# pcb.net
KiCad netlist of a schematic drawn in EasyEDA
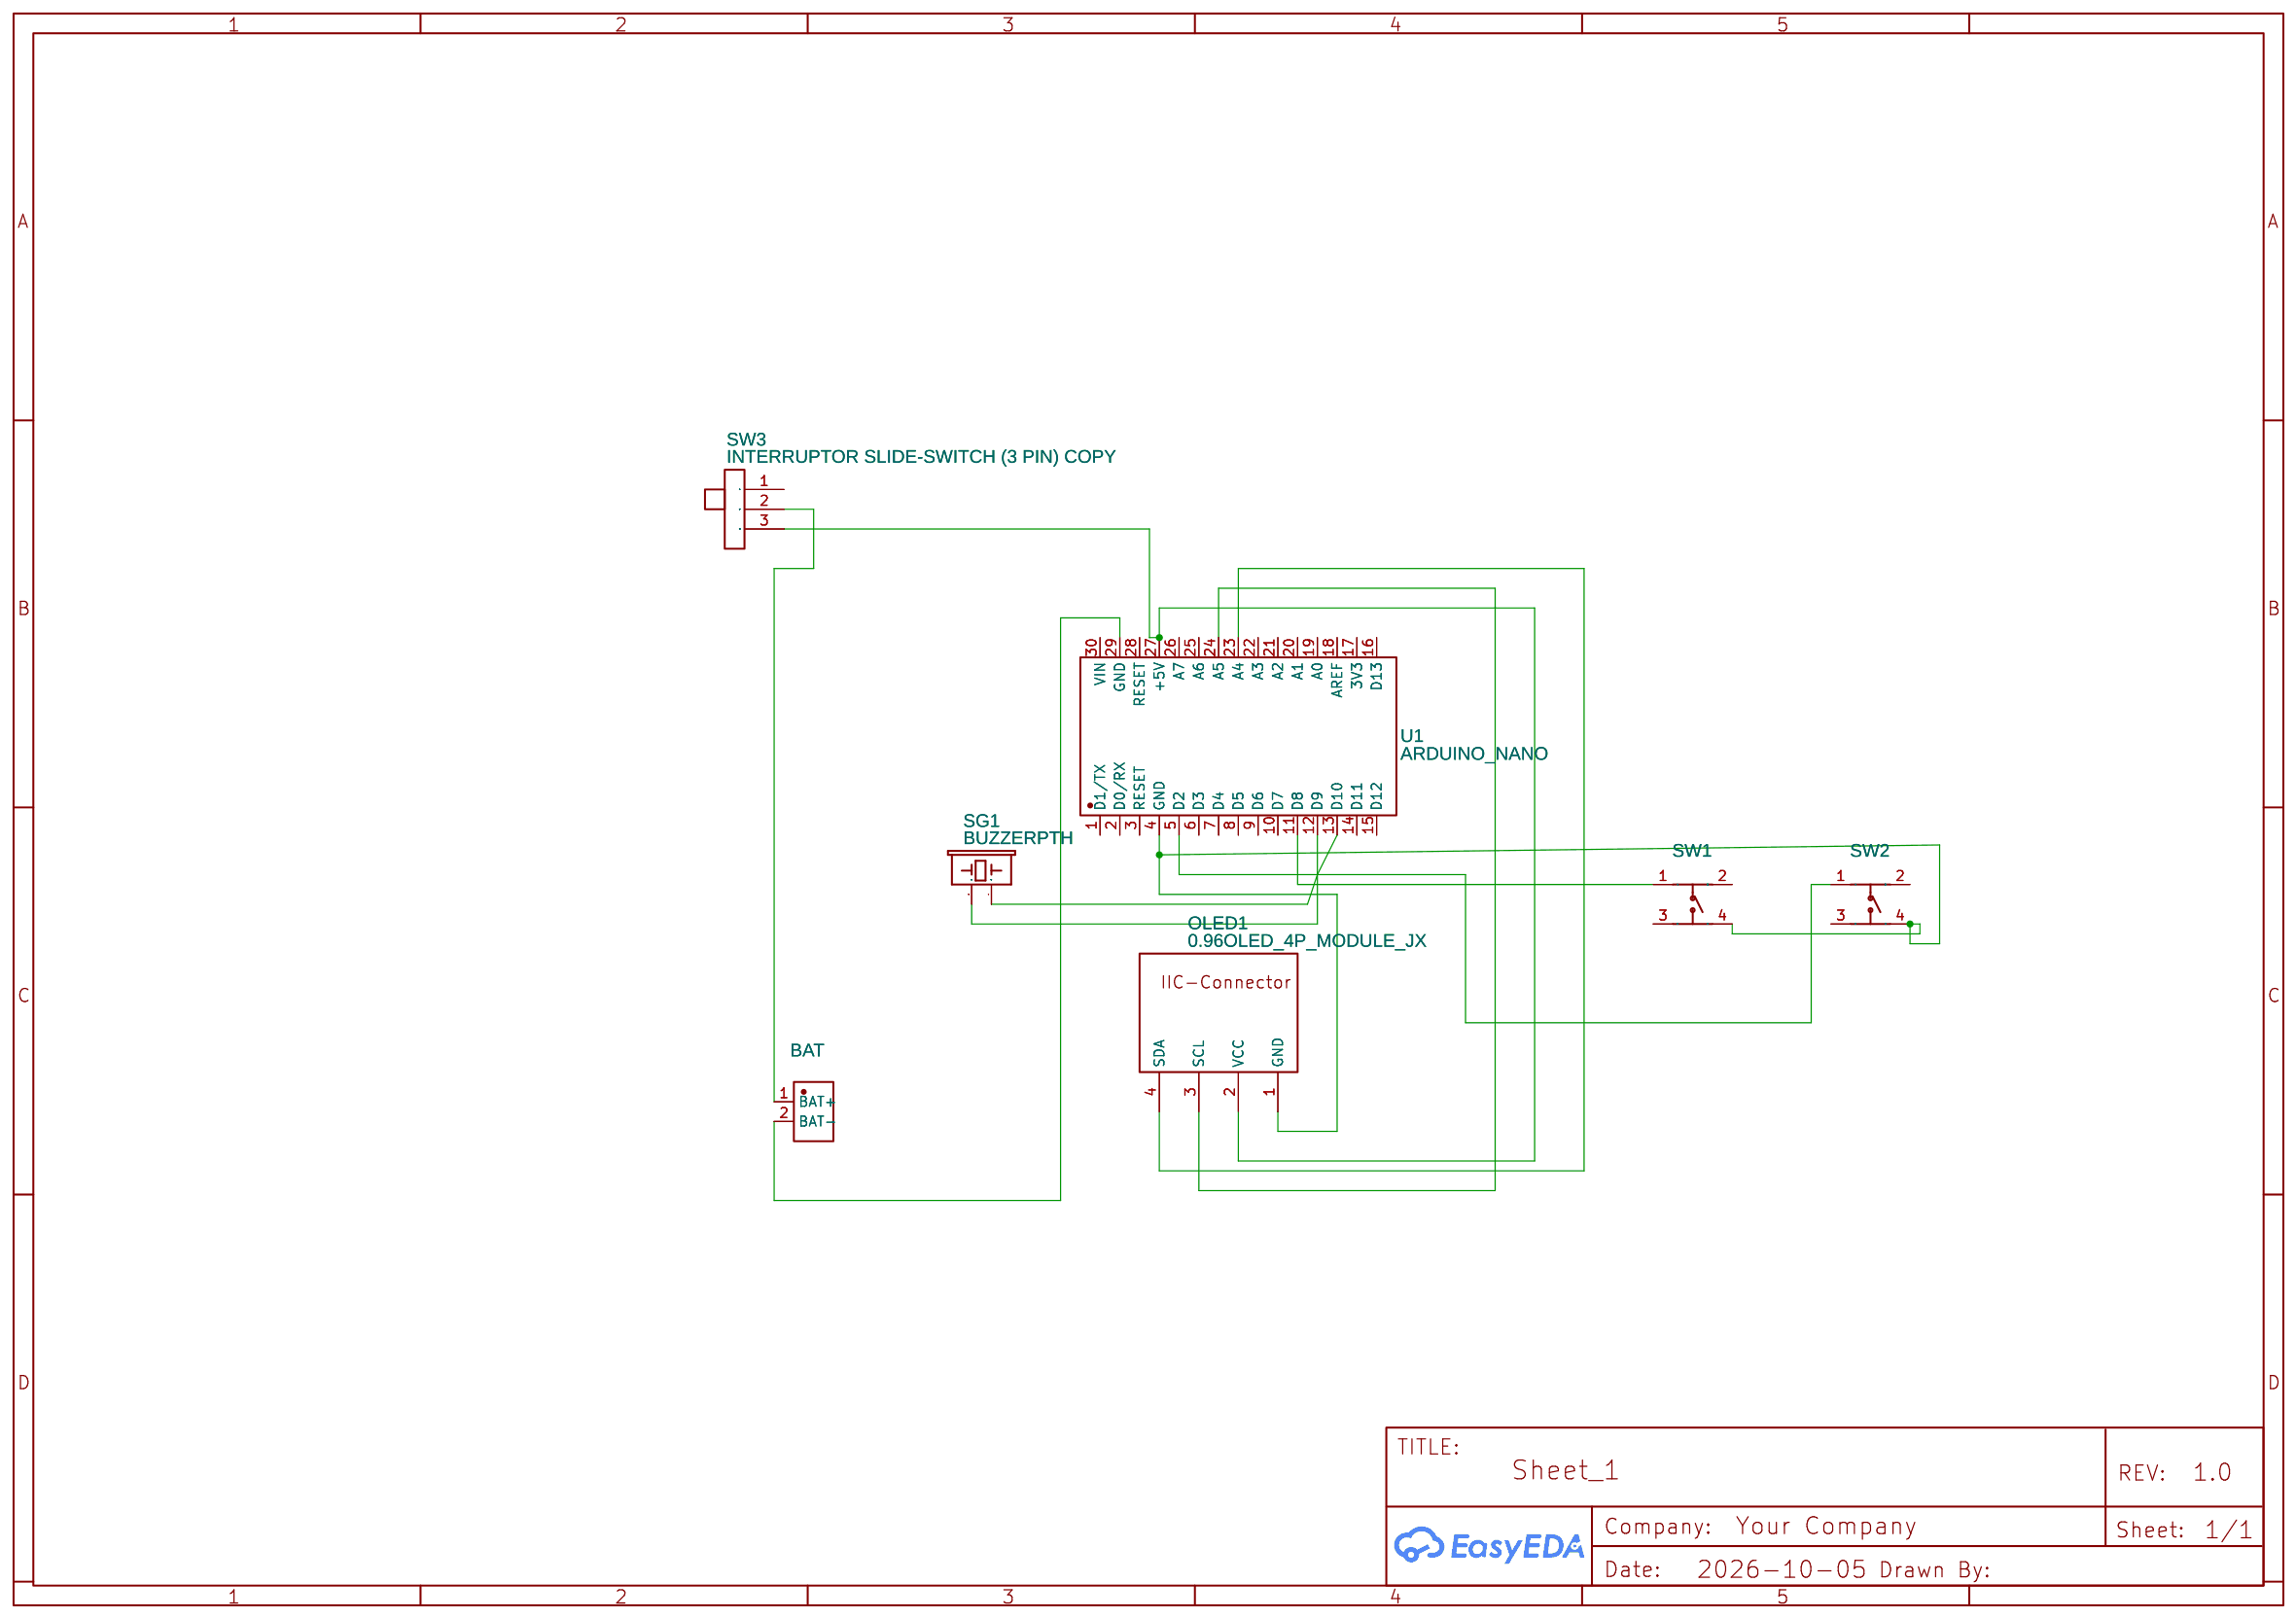
[diagram p0: schematic sheet]

(export (version "E")
  (design (tool "Eeschema 10.0.6"))
  (components
    (comp (ref "BAT")
      (value "880-70-002-10-001101")
      (fields (field (name "Manufacturer") "Preci-Dip"))
      (libsource (lib "") (part "880-70-002-10-001101"))
    )
    (comp (ref "OLED1") (value "0.96OLED_4P_MODULE_JX") (libsource (lib "") (part "0.96OLED_4P_MODULE_JX")))
    (comp (ref "SG1") (value "BUZZERPTH") (libsource (lib "") (part "BUZZERPTH")))
    (comp (ref "SW1")
      (value "SW1")
      (fields (field (name "Manufacturer Part") "Buttontact-6x6mm"))
      (libsource (lib "") (part "BUTTONTACT-6X6MM"))
    )
    (comp (ref "SW2")
      (value "SW2")
      (fields (field (name "Manufacturer Part") "Buttontact-6x6mm"))
      (libsource (lib "") (part "BUTTONTACT-6X6MM"))
    )
    (comp (ref "SW3")
      (value "INTERRUPTOR SLIDE-SWITCH (3 PIN) COPY")
      (fields (field (name "Manufacturer") "A+A Technology Co.,Ltd"))
      (libsource (lib "") (part "INTERRUPTOR SLIDE-SWITCH (3 PIN) COPY"))
    )
    (comp (ref "U1") (value "ARDUINO_NANO") (libsource (lib "") (part "ARDUINO_NANO")))
  )
  (nets
    (net (code "1") (name "Net-(BAT-BAT+)") (class "Default")
      (node (ref "BAT") (pin "1") (pinfunction "BAT+_1") (pintype "unspecified"))
      (node (ref "SW3") (pin "2") (pinfunction "2_2") (pintype "unspecified"))
    )
    (net (code "2") (name "Net-(BAT-BAT-)") (class "Default")
      (node (ref "BAT") (pin "2") (pinfunction "BAT-_2") (pintype "unspecified"))
      (node (ref "U1") (pin "29") (pinfunction "GND_29") (pintype "unspecified"))
    )
    (net (code "3") (name "Net-(OLED1-GND)") (class "Default")
      (node (ref "OLED1") (pin "1") (pinfunction "GND_1") (pintype "unspecified"))
      (node (ref "SW1") (pin "4") (pinfunction "D_4") (pintype "unspecified"))
      (node (ref "SW2") (pin "4") (pinfunction "D_4") (pintype "unspecified"))
      (node (ref "U1") (pin "4") (pinfunction "GND_4") (pintype "unspecified"))
    )
    (net (code "4") (name "Net-(OLED1-SCL)") (class "Default")
      (node (ref "OLED1") (pin "3") (pinfunction "SCL_3") (pintype "unspecified"))
      (node (ref "U1") (pin "24") (pinfunction "A5_24") (pintype "unspecified"))
    )
    (net (code "5") (name "Net-(OLED1-SDA)") (class "Default")
      (node (ref "OLED1") (pin "4") (pinfunction "SDA_4") (pintype "unspecified"))
      (node (ref "U1") (pin "23") (pinfunction "A4_23") (pintype "unspecified"))
    )
    (net (code "6") (name "Net-(OLED1-VCC)") (class "Default")
      (node (ref "OLED1") (pin "2") (pinfunction "VCC_2") (pintype "unspecified"))
      (node (ref "SW3") (pin "3") (pinfunction "3_3") (pintype "unspecified"))
      (node (ref "U1") (pin "27") (pinfunction "+5V_27") (pintype "unspecified"))
    )
    (net (code "7") (name "Net-(SG1-1)") (class "Default")
      (node (ref "SG1") (pin "+") (pinfunction "1_+") (pintype "unspecified"))
      (node (ref "U1") (pin "12") (pinfunction "D9_12") (pintype "unspecified"))
    )
    (net (code "8") (name "Net-(SG1-2)") (class "Default")
      (node (ref "SG1") (pin "-") (pinfunction "2_-") (pintype "unspecified"))
      (node (ref "U1") (pin "13") (pinfunction "D10_13") (pintype "unspecified"))
    )
    (net (code "9") (name "Net-(SW1-A)") (class "Default")
      (node (ref "SW1") (pin "1") (pinfunction "A_1") (pintype "unspecified"))
      (node (ref "U1") (pin "11") (pinfunction "D8_11") (pintype "unspecified"))
    )
    (net (code "10") (name "Net-(SW2-A)") (class "Default")
      (node (ref "SW2") (pin "1") (pinfunction "A_1") (pintype "unspecified"))
      (node (ref "U1") (pin "5") (pinfunction "D2_5") (pintype "unspecified"))
    )
    (net (code "11") (name "unconnected-(SW1-B-Pad2)") (class "Default")
      (node (ref "SW1") (pin "2") (pinfunction "B_2") (pintype "unspecified"))
    )
    (net (code "12") (name "unconnected-(SW1-C-Pad3)") (class "Default")
      (node (ref "SW1") (pin "3") (pinfunction "C_3") (pintype "unspecified"))
    )
    (net (code "13") (name "unconnected-(SW2-B-Pad2)") (class "Default")
      (node (ref "SW2") (pin "2") (pinfunction "B_2") (pintype "unspecified"))
    )
    (net (code "14") (name "unconnected-(SW2-C-Pad3)") (class "Default")
      (node (ref "SW2") (pin "3") (pinfunction "C_3") (pintype "unspecified"))
    )
    (net (code "15") (name "unconnected-(SW3-Pad1)") (class "Default")
      (node (ref "SW3") (pin "1") (pinfunction "1_1") (pintype "unspecified"))
    )
    (net (code "16") (name "unconnected-(U1-3V3-Pad17)") (class "Default")
      (node (ref "U1") (pin "17") (pinfunction "3V3_17") (pintype "unspecified"))
    )
    (net (code "17") (name "unconnected-(U1-A0-Pad19)") (class "Default")
      (node (ref "U1") (pin "19") (pinfunction "A0_19") (pintype "unspecified"))
    )
    (net (code "18") (name "unconnected-(U1-A1-Pad20)") (class "Default")
      (node (ref "U1") (pin "20") (pinfunction "A1_20") (pintype "unspecified"))
    )
    (net (code "19") (name "unconnected-(U1-A2-Pad21)") (class "Default")
      (node (ref "U1") (pin "21") (pinfunction "A2_21") (pintype "unspecified"))
    )
    (net (code "20") (name "unconnected-(U1-A3-Pad22)") (class "Default")
      (node (ref "U1") (pin "22") (pinfunction "A3_22") (pintype "unspecified"))
    )
    (net (code "21") (name "unconnected-(U1-A6-Pad25)") (class "Default")
      (node (ref "U1") (pin "25") (pinfunction "A6_25") (pintype "unspecified"))
    )
    (net (code "22") (name "unconnected-(U1-A7-Pad26)") (class "Default")
      (node (ref "U1") (pin "26") (pinfunction "A7_26") (pintype "unspecified"))
    )
    (net (code "23") (name "unconnected-(U1-AREF-Pad18)") (class "Default")
      (node (ref "U1") (pin "18") (pinfunction "AREF_18") (pintype "unspecified"))
    )
    (net (code "24") (name "unconnected-(U1-D0{slash}RX-Pad2)") (class "Default")
      (node (ref "U1") (pin "2") (pinfunction "D0/RX_2") (pintype "unspecified"))
    )
    (net (code "25") (name "unconnected-(U1-D1{slash}TX-Pad1)") (class "Default")
      (node (ref "U1") (pin "1") (pinfunction "D1/TX_1") (pintype "unspecified"))
    )
    (net (code "26") (name "unconnected-(U1-D3-Pad6)") (class "Default")
      (node (ref "U1") (pin "6") (pinfunction "D3_6") (pintype "unspecified"))
    )
    (net (code "27") (name "unconnected-(U1-D4-Pad7)") (class "Default")
      (node (ref "U1") (pin "7") (pinfunction "D4_7") (pintype "unspecified"))
    )
    (net (code "28") (name "unconnected-(U1-D5-Pad8)") (class "Default")
      (node (ref "U1") (pin "8") (pinfunction "D5_8") (pintype "unspecified"))
    )
    (net (code "29") (name "unconnected-(U1-D6-Pad9)") (class "Default")
      (node (ref "U1") (pin "9") (pinfunction "D6_9") (pintype "unspecified"))
    )
    (net (code "30") (name "unconnected-(U1-D7-Pad10)") (class "Default")
      (node (ref "U1") (pin "10") (pinfunction "D7_10") (pintype "unspecified"))
    )
    (net (code "31") (name "unconnected-(U1-D11-Pad14)") (class "Default")
      (node (ref "U1") (pin "14") (pinfunction "D11_14") (pintype "unspecified"))
    )
    (net (code "32") (name "unconnected-(U1-D12-Pad15)") (class "Default")
      (node (ref "U1") (pin "15") (pinfunction "D12_15") (pintype "unspecified"))
    )
    (net (code "33") (name "unconnected-(U1-D13-Pad16)") (class "Default")
      (node (ref "U1") (pin "16") (pinfunction "D13_16") (pintype "unspecified"))
    )
    (net (code "34") (name "unconnected-(U1-RESET-Pad3)") (class "Default")
      (node (ref "U1") (pin "3") (pinfunction "RESET_3") (pintype "unspecified"))
    )
    (net (code "35") (name "unconnected-(U1-RESET-Pad28)") (class "Default")
      (node (ref "U1") (pin "28") (pinfunction "RESET_28") (pintype "unspecified"))
    )
    (net (code "36") (name "unconnected-(U1-VIN-Pad30)") (class "Default")
      (node (ref "U1") (pin "30") (pinfunction "VIN_30") (pintype "unspecified"))
    )
  )
)
